# 04-Switch_RJ45.net
KiCad netlist of a schematic drawn in Altium Designer
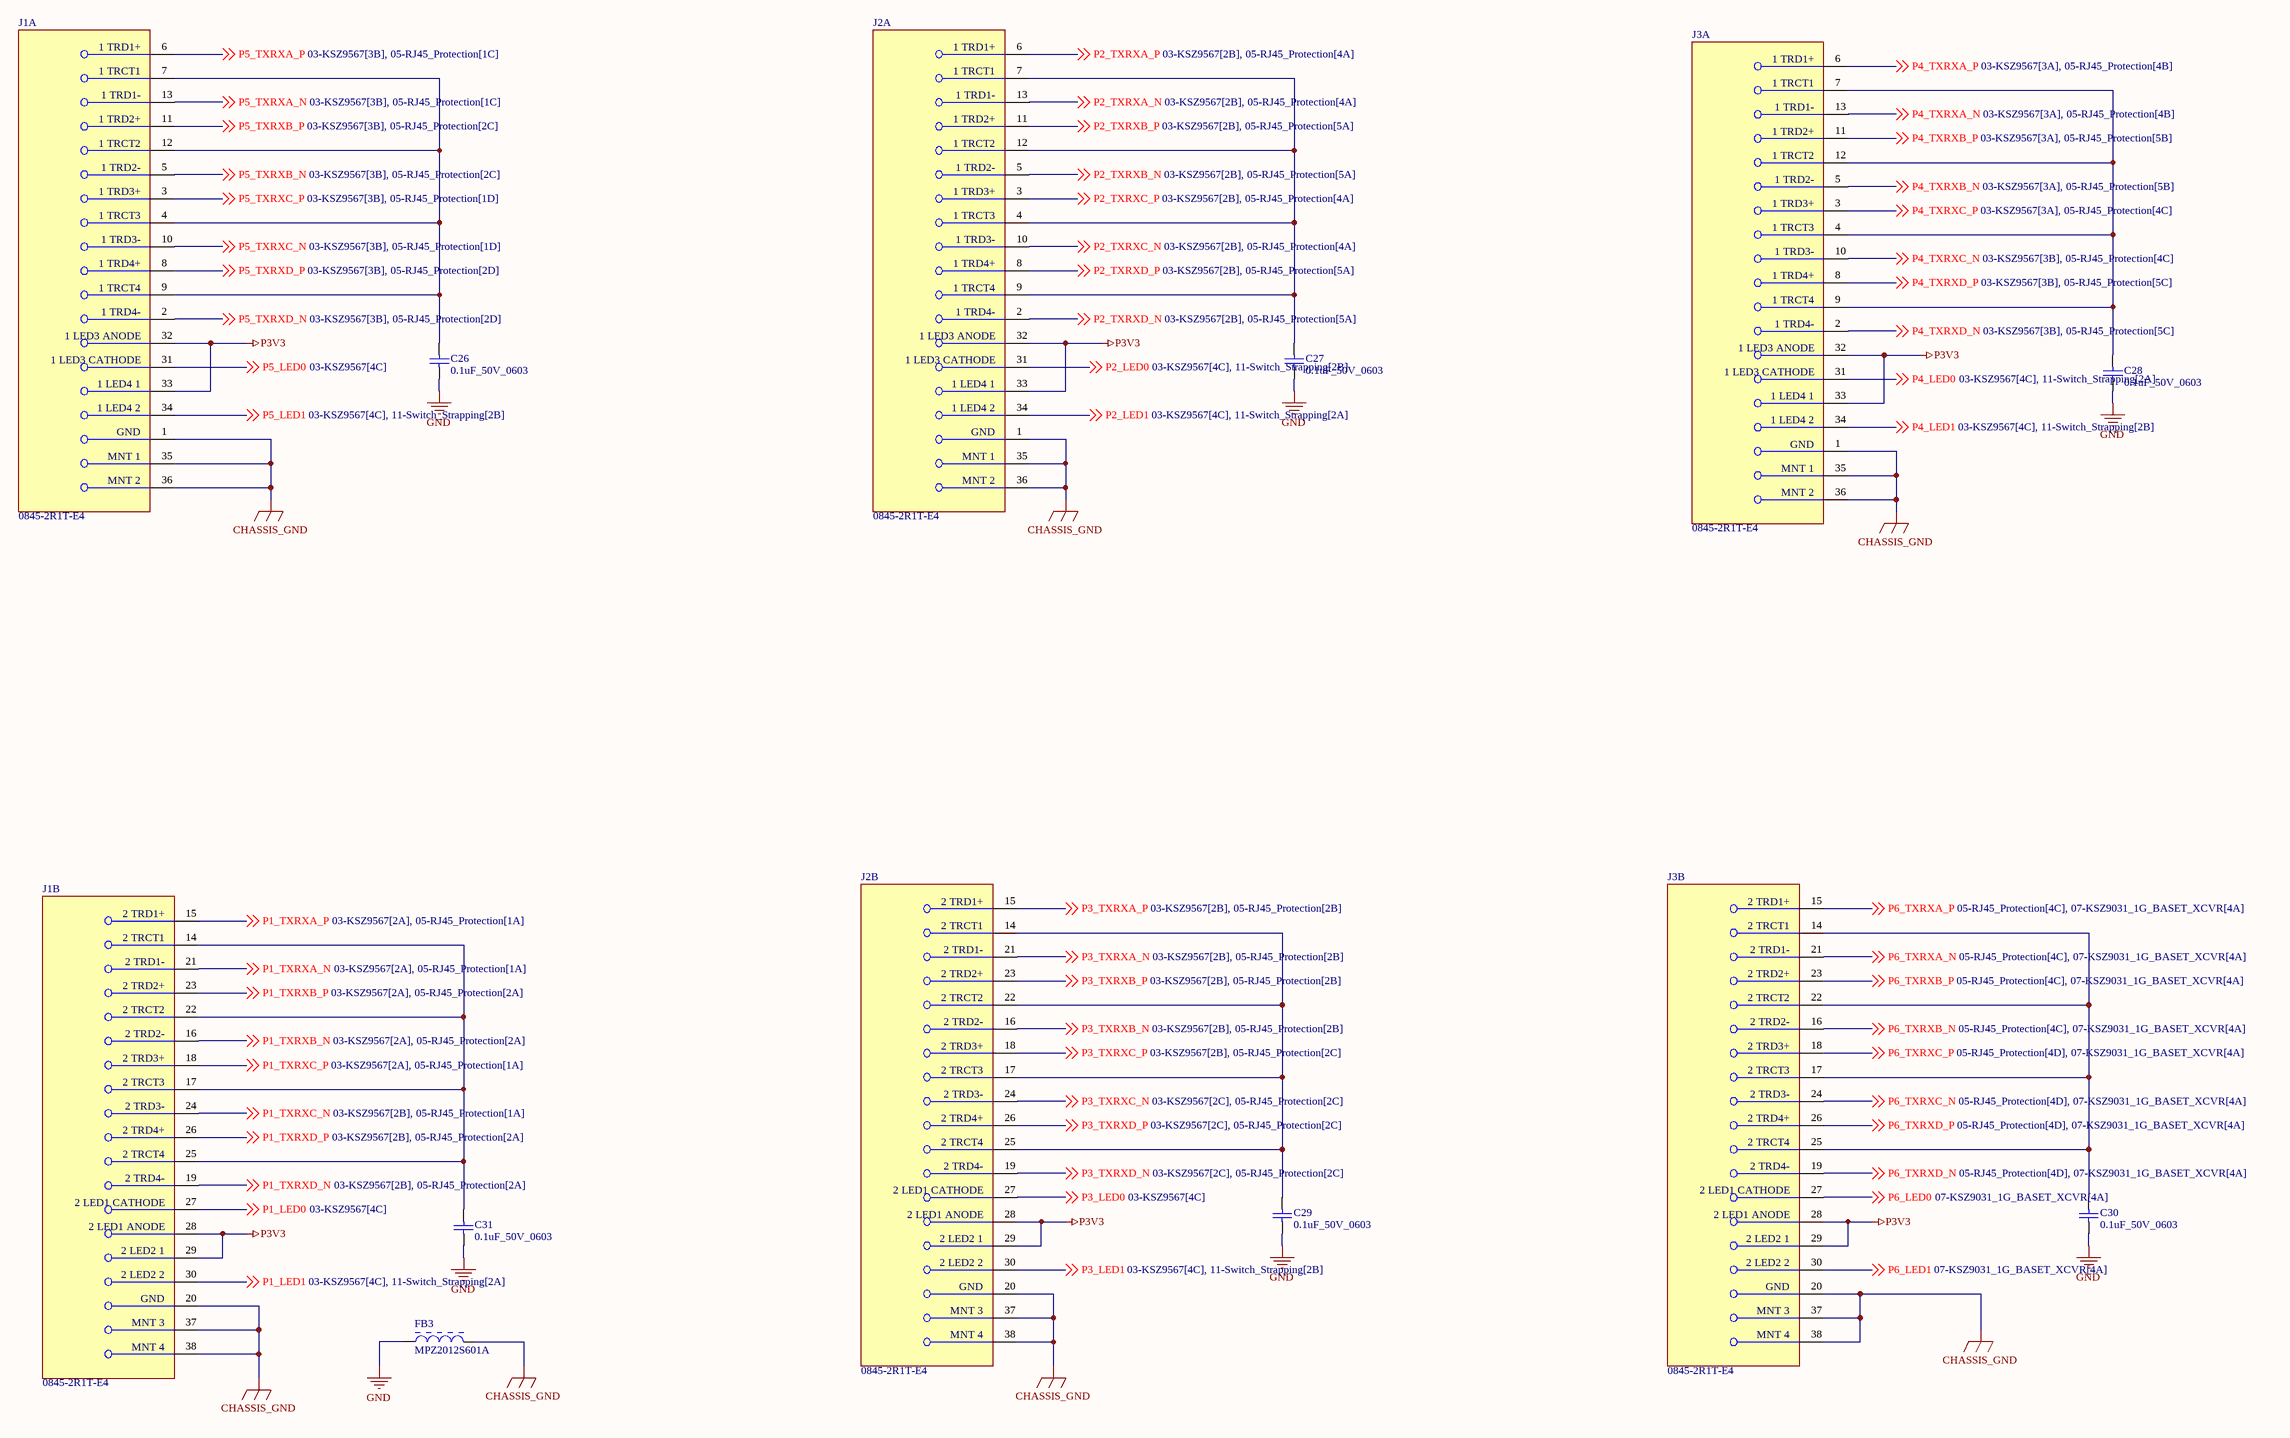
[diagram p0: 04-Switch_RJ45.SchDoc]

(export (version "E")
  (design (tool "Eeschema 10.0.6"))
  (components
    (comp (ref "C26")
      (value "0.1uF_50V_0603")
      (footprint "CAPC1608X90X35ML10T15")
      (description "Chip Capacitor, 0.1 uF, +/- 10%, 50 V, -55 to 125 degC, 0603 (1608 Metric), RoHS, Tape and Reel")
      (fields (field (name "TOLERANCE") "10%") (field (name "VOLTAGE") "50V"))
      (libsource (lib "Altium Content Vault") (part "CAP-NP-2"))
    )
    (comp (ref "C27")
      (value "0.1uF_50V_0603")
      (footprint "CAPC1608X90X35ML10T15")
      (description "Chip Capacitor, 0.1 uF, +/- 10%, 50 V, -55 to 125 degC, 0603 (1608 Metric), RoHS, Tape and Reel")
      (fields (field (name "TOLERANCE") "10%") (field (name "VOLTAGE") "50V"))
      (libsource (lib "Altium Content Vault") (part "CAP-NP-2"))
    )
    (comp (ref "C28")
      (value "0.1uF_50V_0603")
      (footprint "CAPC1608X90X35ML10T15")
      (description "Chip Capacitor, 0.1 uF, +/- 10%, 50 V, -55 to 125 degC, 0603 (1608 Metric), RoHS, Tape and Reel")
      (fields (field (name "TOLERANCE") "10%") (field (name "VOLTAGE") "50V"))
      (libsource (lib "Altium Content Vault") (part "CAP-NP-2"))
    )
    (comp (ref "C29")
      (value "0.1uF_50V_0603")
      (footprint "CAPC1608X90X35ML10T15")
      (description "Chip Capacitor, 0.1 uF, +/- 10%, 50 V, -55 to 125 degC, 0603 (1608 Metric), RoHS, Tape and Reel")
      (fields (field (name "TOLERANCE") "10%") (field (name "VOLTAGE") "50V"))
      (libsource (lib "Altium Content Vault") (part "CAP-NP-2"))
    )
    (comp (ref "C30")
      (value "0.1uF_50V_0603")
      (footprint "CAPC1608X90X35ML10T15")
      (description "Chip Capacitor, 0.1 uF, +/- 10%, 50 V, -55 to 125 degC, 0603 (1608 Metric), RoHS, Tape and Reel")
      (fields (field (name "TOLERANCE") "10%") (field (name "VOLTAGE") "50V"))
      (libsource (lib "Altium Content Vault") (part "CAP-NP-2"))
    )
    (comp (ref "C31")
      (value "0.1uF_50V_0603")
      (footprint "CAPC1608X90X35ML10T15")
      (description "Chip Capacitor, 0.1 uF, +/- 10%, 50 V, -55 to 125 degC, 0603 (1608 Metric), RoHS, Tape and Reel")
      (fields (field (name "TOLERANCE") "10%") (field (name "VOLTAGE") "50V"))
      (libsource (lib "Altium Content Vault") (part "CAP-NP-2"))
    )
    (comp (ref "FB3")
      (value "MPZ2012S601A")
      (footprint "TDK-MPZ2012_V")
      (fields (field (name "TOLERANCE") "25%") (field (name "MANUFACTURER") "TDK"))
      (libsource (lib "Altium Content Vault") (part "BEAD-2"))
    )
    (comp (ref "J1")
      (value "0845-2R1T-E4")
      (footprint "FP-0845-2R1T-E4-MFG")
      (description "CONN MAGJACK 2PORT 1000 BASE-T")
      (fields
        (field (name "MANUFACTURER") "Bel Fuse")
        (field (name "OCTOPART") "https://octopart.com/0845-2r1t-e4-bel+fuse-10528446")
      )
      (libsource (lib "Altium Content Vault") (part "f9656fd82f206e5257674b7adff4f5e"))
    )
    (comp (ref "J2")
      (value "0845-2R1T-E4")
      (footprint "FP-0845-2R1T-E4-MFG")
      (description "CONN MAGJACK 2PORT 1000 BASE-T")
      (fields
        (field (name "MANUFACTURER") "Bel Fuse")
        (field (name "OCTOPART") "https://octopart.com/0845-2r1t-e4-bel+fuse-10528446")
      )
      (libsource (lib "Altium Content Vault") (part "f9656fd82f206e5257674b7adff4f5e"))
    )
    (comp (ref "J3")
      (value "0845-2R1T-E4")
      (footprint "FP-0845-2R1T-E4-MFG")
      (description "CONN MAGJACK 2PORT 1000 BASE-T")
      (fields
        (field (name "MANUFACTURER") "Bel Fuse")
        (field (name "OCTOPART") "https://octopart.com/0845-2r1t-e4-bel+fuse-10528446")
      )
      (libsource (lib "Altium Content Vault") (part "f9656fd82f206e5257674b7adff4f5e"))
    )
  )
  (nets
    (net (code "1") (name "CHASSIS_GND") (class "Default")
      (node (ref "FB3") (pin "2") (pinfunction "2_2") (pintype "passive"))
      (node (ref "J1") (pin "1") (pinfunction "GND_1") (pintype "power_in"))
      (node (ref "J1") (pin "20") (pinfunction "GND_20") (pintype "power_in"))
      (node (ref "J1") (pin "35") (pinfunction "MNT_1_35") (pintype "passive"))
      (node (ref "J1") (pin "36") (pinfunction "MNT_2_36") (pintype "passive"))
      (node (ref "J1") (pin "37") (pinfunction "MNT_3_37") (pintype "passive"))
      (node (ref "J1") (pin "38") (pinfunction "MNT_4_38") (pintype "passive"))
      (node (ref "J2") (pin "1") (pinfunction "GND_1") (pintype "power_in"))
      (node (ref "J2") (pin "20") (pinfunction "GND_20") (pintype "power_in"))
      (node (ref "J2") (pin "35") (pinfunction "MNT_1_35") (pintype "passive"))
      (node (ref "J2") (pin "36") (pinfunction "MNT_2_36") (pintype "passive"))
      (node (ref "J2") (pin "37") (pinfunction "MNT_3_37") (pintype "passive"))
      (node (ref "J2") (pin "38") (pinfunction "MNT_4_38") (pintype "passive"))
      (node (ref "J3") (pin "1") (pinfunction "GND_1") (pintype "power_in"))
      (node (ref "J3") (pin "20") (pinfunction "GND_20") (pintype "power_in"))
      (node (ref "J3") (pin "35") (pinfunction "MNT_1_35") (pintype "passive"))
      (node (ref "J3") (pin "36") (pinfunction "MNT_2_36") (pintype "passive"))
      (node (ref "J3") (pin "37") (pinfunction "MNT_3_37") (pintype "passive"))
      (node (ref "J3") (pin "38") (pinfunction "MNT_4_38") (pintype "passive"))
    )
    (net (code "2") (name "GND") (class "Default")
      (node (ref "C26") (pin "1") (pinfunction "1_1") (pintype "passive"))
      (node (ref "C27") (pin "1") (pinfunction "1_1") (pintype "passive"))
      (node (ref "C28") (pin "1") (pinfunction "1_1") (pintype "passive"))
      (node (ref "C29") (pin "1") (pinfunction "1_1") (pintype "passive"))
      (node (ref "C30") (pin "1") (pinfunction "1_1") (pintype "passive"))
      (node (ref "C31") (pin "1") (pinfunction "1_1") (pintype "passive"))
      (node (ref "FB3") (pin "1") (pinfunction "1_1") (pintype "passive"))
    )
    (net (code "3") (name "Net-(J1A-1_TRCT1)") (class "Default")
      (node (ref "C26") (pin "2") (pinfunction "2_2") (pintype "passive"))
      (node (ref "J1") (pin "12") (pinfunction "1_TRCT2_12") (pintype "passive"))
      (node (ref "J1") (pin "4") (pinfunction "1_TRCT3_4") (pintype "passive"))
      (node (ref "J1") (pin "7") (pinfunction "1_TRCT1_7") (pintype "passive"))
      (node (ref "J1") (pin "9") (pinfunction "1_TRCT4_9") (pintype "passive"))
    )
    (net (code "4") (name "Net-(J1B-2_TRCT1)") (class "Default")
      (node (ref "C31") (pin "2") (pinfunction "2_2") (pintype "passive"))
      (node (ref "J1") (pin "14") (pinfunction "2_TRCT1_14") (pintype "passive"))
      (node (ref "J1") (pin "17") (pinfunction "2_TRCT3_17") (pintype "passive"))
      (node (ref "J1") (pin "22") (pinfunction "2_TRCT2_22") (pintype "passive"))
      (node (ref "J1") (pin "25") (pinfunction "2_TRCT4_25") (pintype "passive"))
    )
    (net (code "5") (name "Net-(J2A-1_TRCT1)") (class "Default")
      (node (ref "C27") (pin "2") (pinfunction "2_2") (pintype "passive"))
      (node (ref "J2") (pin "12") (pinfunction "1_TRCT2_12") (pintype "passive"))
      (node (ref "J2") (pin "4") (pinfunction "1_TRCT3_4") (pintype "passive"))
      (node (ref "J2") (pin "7") (pinfunction "1_TRCT1_7") (pintype "passive"))
      (node (ref "J2") (pin "9") (pinfunction "1_TRCT4_9") (pintype "passive"))
    )
    (net (code "6") (name "Net-(J2B-2_TRCT1)") (class "Default")
      (node (ref "C29") (pin "2") (pinfunction "2_2") (pintype "passive"))
      (node (ref "J2") (pin "14") (pinfunction "2_TRCT1_14") (pintype "passive"))
      (node (ref "J2") (pin "17") (pinfunction "2_TRCT3_17") (pintype "passive"))
      (node (ref "J2") (pin "22") (pinfunction "2_TRCT2_22") (pintype "passive"))
      (node (ref "J2") (pin "25") (pinfunction "2_TRCT4_25") (pintype "passive"))
    )
    (net (code "7") (name "Net-(J3A-1_TRCT1)") (class "Default")
      (node (ref "C28") (pin "2") (pinfunction "2_2") (pintype "passive"))
      (node (ref "J3") (pin "12") (pinfunction "1_TRCT2_12") (pintype "passive"))
      (node (ref "J3") (pin "4") (pinfunction "1_TRCT3_4") (pintype "passive"))
      (node (ref "J3") (pin "7") (pinfunction "1_TRCT1_7") (pintype "passive"))
      (node (ref "J3") (pin "9") (pinfunction "1_TRCT4_9") (pintype "passive"))
    )
    (net (code "8") (name "Net-(J3B-2_TRCT1)") (class "Default")
      (node (ref "C30") (pin "2") (pinfunction "2_2") (pintype "passive"))
      (node (ref "J3") (pin "14") (pinfunction "2_TRCT1_14") (pintype "passive"))
      (node (ref "J3") (pin "17") (pinfunction "2_TRCT3_17") (pintype "passive"))
      (node (ref "J3") (pin "22") (pinfunction "2_TRCT2_22") (pintype "passive"))
      (node (ref "J3") (pin "25") (pinfunction "2_TRCT4_25") (pintype "passive"))
    )
    (net (code "9") (name "P1_LED0") (class "Default")
      (node (ref "J1") (pin "27") (pinfunction "2_LED1_CATHODE_27") (pintype "passive"))
    )
    (net (code "10") (name "P1_LED1") (class "Default")
      (node (ref "J1") (pin "30") (pinfunction "2_LED2_2_30") (pintype "passive"))
    )
    (net (code "11") (name "P1_TXRXA_N") (class "Default")
      (node (ref "J1") (pin "21") (pinfunction "2_TRD1-_21") (pintype "passive"))
    )
    (net (code "12") (name "P1_TXRXA_P") (class "Default")
      (node (ref "J1") (pin "15") (pinfunction "2_TRD1+_15") (pintype "passive"))
    )
    (net (code "13") (name "P1_TXRXB_N") (class "Default")
      (node (ref "J1") (pin "16") (pinfunction "2_TRD2-_16") (pintype "passive"))
    )
    (net (code "14") (name "P1_TXRXB_P") (class "Default")
      (node (ref "J1") (pin "23") (pinfunction "2_TRD2+_23") (pintype "passive"))
    )
    (net (code "15") (name "P1_TXRXC_N") (class "Default")
      (node (ref "J1") (pin "24") (pinfunction "2_TRD3-_24") (pintype "passive"))
    )
    (net (code "16") (name "P1_TXRXC_P") (class "Default")
      (node (ref "J1") (pin "18") (pinfunction "2_TRD3+_18") (pintype "passive"))
    )
    (net (code "17") (name "P1_TXRXD_N") (class "Default")
      (node (ref "J1") (pin "19") (pinfunction "2_TRD4-_19") (pintype "passive"))
    )
    (net (code "18") (name "P1_TXRXD_P") (class "Default")
      (node (ref "J1") (pin "26") (pinfunction "2_TRD4+_26") (pintype "passive"))
    )
    (net (code "19") (name "P2_LED0") (class "Default")
      (node (ref "J2") (pin "31") (pinfunction "1_LED3_CATHODE_31") (pintype "passive"))
    )
    (net (code "20") (name "P2_LED1") (class "Default")
      (node (ref "J2") (pin "34") (pinfunction "1_LED4_2_34") (pintype "passive"))
    )
    (net (code "21") (name "P2_TXRXA_N") (class "Default")
      (node (ref "J2") (pin "13") (pinfunction "1_TRD1-_13") (pintype "passive"))
    )
    (net (code "22") (name "P2_TXRXA_P") (class "Default")
      (node (ref "J2") (pin "6") (pinfunction "1_TRD1+_6") (pintype "passive"))
    )
    (net (code "23") (name "P2_TXRXB_N") (class "Default")
      (node (ref "J2") (pin "5") (pinfunction "1_TRD2-_5") (pintype "passive"))
    )
    (net (code "24") (name "P2_TXRXB_P") (class "Default")
      (node (ref "J2") (pin "11") (pinfunction "1_TRD2+_11") (pintype "passive"))
    )
    (net (code "25") (name "P2_TXRXC_N") (class "Default")
      (node (ref "J2") (pin "10") (pinfunction "1_TRD3-_10") (pintype "passive"))
    )
    (net (code "26") (name "P2_TXRXC_P") (class "Default")
      (node (ref "J2") (pin "3") (pinfunction "1_TRD3+_3") (pintype "passive"))
    )
    (net (code "27") (name "P2_TXRXD_N") (class "Default")
      (node (ref "J2") (pin "2") (pinfunction "1_TRD4-_2") (pintype "passive"))
    )
    (net (code "28") (name "P2_TXRXD_P") (class "Default")
      (node (ref "J2") (pin "8") (pinfunction "1_TRD4+_8") (pintype "passive"))
    )
    (net (code "29") (name "P3V3") (class "Default")
      (node (ref "J1") (pin "28") (pinfunction "2_LED1_ANODE_28") (pintype "passive"))
      (node (ref "J1") (pin "29") (pinfunction "2_LED2_1_29") (pintype "passive"))
      (node (ref "J1") (pin "32") (pinfunction "1_LED3_ANODE_32") (pintype "passive"))
      (node (ref "J1") (pin "33") (pinfunction "1_LED4_1_33") (pintype "passive"))
      (node (ref "J2") (pin "28") (pinfunction "2_LED1_ANODE_28") (pintype "passive"))
      (node (ref "J2") (pin "29") (pinfunction "2_LED2_1_29") (pintype "passive"))
      (node (ref "J2") (pin "32") (pinfunction "1_LED3_ANODE_32") (pintype "passive"))
      (node (ref "J2") (pin "33") (pinfunction "1_LED4_1_33") (pintype "passive"))
      (node (ref "J3") (pin "28") (pinfunction "2_LED1_ANODE_28") (pintype "passive"))
      (node (ref "J3") (pin "29") (pinfunction "2_LED2_1_29") (pintype "passive"))
      (node (ref "J3") (pin "32") (pinfunction "1_LED3_ANODE_32") (pintype "passive"))
      (node (ref "J3") (pin "33") (pinfunction "1_LED4_1_33") (pintype "passive"))
    )
    (net (code "30") (name "P3_LED0") (class "Default")
      (node (ref "J2") (pin "27") (pinfunction "2_LED1_CATHODE_27") (pintype "passive"))
    )
    (net (code "31") (name "P3_LED1") (class "Default")
      (node (ref "J2") (pin "30") (pinfunction "2_LED2_2_30") (pintype "passive"))
    )
    (net (code "32") (name "P3_TXRXA_N") (class "Default")
      (node (ref "J2") (pin "21") (pinfunction "2_TRD1-_21") (pintype "passive"))
    )
    (net (code "33") (name "P3_TXRXA_P") (class "Default")
      (node (ref "J2") (pin "15") (pinfunction "2_TRD1+_15") (pintype "passive"))
    )
    (net (code "34") (name "P3_TXRXB_N") (class "Default")
      (node (ref "J2") (pin "16") (pinfunction "2_TRD2-_16") (pintype "passive"))
    )
    (net (code "35") (name "P3_TXRXB_P") (class "Default")
      (node (ref "J2") (pin "23") (pinfunction "2_TRD2+_23") (pintype "passive"))
    )
    (net (code "36") (name "P3_TXRXC_N") (class "Default")
      (node (ref "J2") (pin "24") (pinfunction "2_TRD3-_24") (pintype "passive"))
    )
    (net (code "37") (name "P3_TXRXC_P") (class "Default")
      (node (ref "J2") (pin "18") (pinfunction "2_TRD3+_18") (pintype "passive"))
    )
    (net (code "38") (name "P3_TXRXD_N") (class "Default")
      (node (ref "J2") (pin "19") (pinfunction "2_TRD4-_19") (pintype "passive"))
    )
    (net (code "39") (name "P3_TXRXD_P") (class "Default")
      (node (ref "J2") (pin "26") (pinfunction "2_TRD4+_26") (pintype "passive"))
    )
    (net (code "40") (name "P4_LED0") (class "Default")
      (node (ref "J3") (pin "31") (pinfunction "1_LED3_CATHODE_31") (pintype "passive"))
    )
    (net (code "41") (name "P4_LED1") (class "Default")
      (node (ref "J3") (pin "34") (pinfunction "1_LED4_2_34") (pintype "passive"))
    )
    (net (code "42") (name "P4_TXRXA_N") (class "Default")
      (node (ref "J3") (pin "13") (pinfunction "1_TRD1-_13") (pintype "passive"))
    )
    (net (code "43") (name "P4_TXRXA_P") (class "Default")
      (node (ref "J3") (pin "6") (pinfunction "1_TRD1+_6") (pintype "passive"))
    )
    (net (code "44") (name "P4_TXRXB_N") (class "Default")
      (node (ref "J3") (pin "5") (pinfunction "1_TRD2-_5") (pintype "passive"))
    )
    (net (code "45") (name "P4_TXRXB_P") (class "Default")
      (node (ref "J3") (pin "11") (pinfunction "1_TRD2+_11") (pintype "passive"))
    )
    (net (code "46") (name "P4_TXRXC_N") (class "Default")
      (node (ref "J3") (pin "10") (pinfunction "1_TRD3-_10") (pintype "passive"))
    )
    (net (code "47") (name "P4_TXRXC_P") (class "Default")
      (node (ref "J3") (pin "3") (pinfunction "1_TRD3+_3") (pintype "passive"))
    )
    (net (code "48") (name "P4_TXRXD_N") (class "Default")
      (node (ref "J3") (pin "2") (pinfunction "1_TRD4-_2") (pintype "passive"))
    )
    (net (code "49") (name "P4_TXRXD_P") (class "Default")
      (node (ref "J3") (pin "8") (pinfunction "1_TRD4+_8") (pintype "passive"))
    )
    (net (code "50") (name "P5_LED0") (class "Default")
      (node (ref "J1") (pin "31") (pinfunction "1_LED3_CATHODE_31") (pintype "passive"))
    )
    (net (code "51") (name "P5_LED1") (class "Default")
      (node (ref "J1") (pin "34") (pinfunction "1_LED4_2_34") (pintype "passive"))
    )
    (net (code "52") (name "P5_TXRXA_N") (class "Default")
      (node (ref "J1") (pin "13") (pinfunction "1_TRD1-_13") (pintype "passive"))
    )
    (net (code "53") (name "P5_TXRXA_P") (class "Default")
      (node (ref "J1") (pin "6") (pinfunction "1_TRD1+_6") (pintype "passive"))
    )
    (net (code "54") (name "P5_TXRXB_N") (class "Default")
      (node (ref "J1") (pin "5") (pinfunction "1_TRD2-_5") (pintype "passive"))
    )
    (net (code "55") (name "P5_TXRXB_P") (class "Default")
      (node (ref "J1") (pin "11") (pinfunction "1_TRD2+_11") (pintype "passive"))
    )
    (net (code "56") (name "P5_TXRXC_N") (class "Default")
      (node (ref "J1") (pin "10") (pinfunction "1_TRD3-_10") (pintype "passive"))
    )
    (net (code "57") (name "P5_TXRXC_P") (class "Default")
      (node (ref "J1") (pin "3") (pinfunction "1_TRD3+_3") (pintype "passive"))
    )
    (net (code "58") (name "P5_TXRXD_N") (class "Default")
      (node (ref "J1") (pin "2") (pinfunction "1_TRD4-_2") (pintype "passive"))
    )
    (net (code "59") (name "P5_TXRXD_P") (class "Default")
      (node (ref "J1") (pin "8") (pinfunction "1_TRD4+_8") (pintype "passive"))
    )
    (net (code "60") (name "P6_LED0") (class "Default")
      (node (ref "J3") (pin "27") (pinfunction "2_LED1_CATHODE_27") (pintype "passive"))
    )
    (net (code "61") (name "P6_LED1") (class "Default")
      (node (ref "J3") (pin "30") (pinfunction "2_LED2_2_30") (pintype "passive"))
    )
    (net (code "62") (name "P6_TXRXA_N") (class "Default")
      (node (ref "J3") (pin "21") (pinfunction "2_TRD1-_21") (pintype "passive"))
    )
    (net (code "63") (name "P6_TXRXA_P") (class "Default")
      (node (ref "J3") (pin "15") (pinfunction "2_TRD1+_15") (pintype "passive"))
    )
    (net (code "64") (name "P6_TXRXB_N") (class "Default")
      (node (ref "J3") (pin "16") (pinfunction "2_TRD2-_16") (pintype "passive"))
    )
    (net (code "65") (name "P6_TXRXB_P") (class "Default")
      (node (ref "J3") (pin "23") (pinfunction "2_TRD2+_23") (pintype "passive"))
    )
    (net (code "66") (name "P6_TXRXC_N") (class "Default")
      (node (ref "J3") (pin "24") (pinfunction "2_TRD3-_24") (pintype "passive"))
    )
    (net (code "67") (name "P6_TXRXC_P") (class "Default")
      (node (ref "J3") (pin "18") (pinfunction "2_TRD3+_18") (pintype "passive"))
    )
    (net (code "68") (name "P6_TXRXD_N") (class "Default")
      (node (ref "J3") (pin "19") (pinfunction "2_TRD4-_19") (pintype "passive"))
    )
    (net (code "69") (name "P6_TXRXD_P") (class "Default")
      (node (ref "J3") (pin "26") (pinfunction "2_TRD4+_26") (pintype "passive"))
    )
  )
)
